# Brightside_Telemetry_stm_rev2.net
KiCad netlist of a schematic drawn in Altium Designer
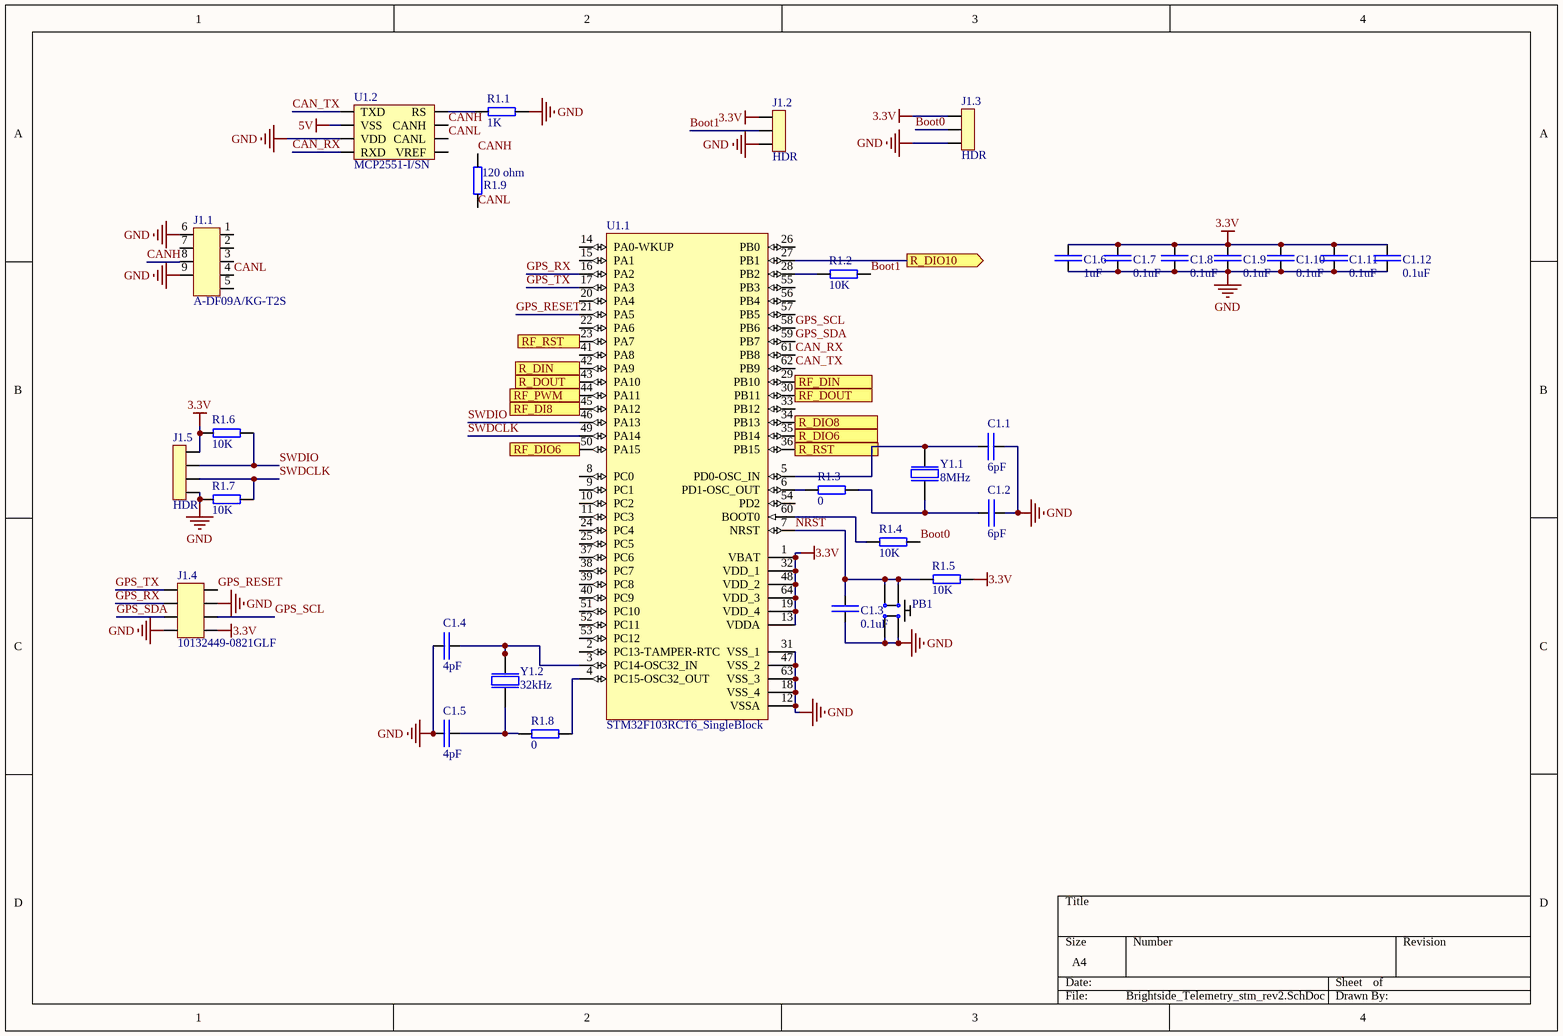
[diagram p0: Brightside_Telemetry_stm_rev2.SchDoc]

(export (version "E")
  (design (tool "Eeschema 10.0.6"))
  (components
    (comp (ref "C1.1")
      (value "6pF")
      (footprint "0603")
      (description "CAP CER 6PF 50V C0G/NPO 0603")
      (fields
        (field (name "MANUFACTURER") "Yageo")
        (field (name "MANUFACTURER PART NUMBER") "CC0603DRNPO9BN6R0")
      )
      (libsource (lib "Capacitors") (part "CC0603DRNPO9BN6R0"))
    )
    (comp (ref "C1.2")
      (value "6pF")
      (footprint "0603")
      (description "CAP CER 6PF 50V C0G/NPO 0603")
      (fields
        (field (name "MANUFACTURER") "Yageo")
        (field (name "MANUFACTURER PART NUMBER") "CC0603DRNPO9BN6R0")
      )
      (libsource (lib "Capacitors") (part "CC0603DRNPO9BN6R0"))
    )
    (comp (ref "C1.3")
      (value "0.1uF")
      (footprint "C0805")
      (description "CAP CER 0.1UF 50V X7R 0805")
      (fields
        (field (name "MANUFACTURER") "Samsung")
        (field (name "MANUFACTURER PART NUMBER") "CL21B104KBCWPNC")
      )
      (libsource (lib "Capacitors") (part "CL21B104KBCWPNC"))
    )
    (comp (ref "C1.4")
      (value "4pF")
      (footprint "0603")
      (description "CAP CER 4PF 50V C0G/NPO 0603")
      (fields
        (field (name "MANUFACTURER") "Yageo")
        (field (name "MANUFACTURER PART NUMBER") "CC0603CRNPO9BN4R0")
      )
      (libsource (lib "Capacitors") (part "CC0603CRNPO9BN4R0"))
    )
    (comp (ref "C1.5")
      (value "4pF")
      (footprint "0603")
      (description "CAP CER 4PF 50V C0G/NPO 0603")
      (fields
        (field (name "MANUFACTURER") "Yageo")
        (field (name "MANUFACTURER PART NUMBER") "CC0603CRNPO9BN4R0")
      )
      (libsource (lib "Capacitors") (part "CC0603CRNPO9BN4R0"))
    )
    (comp (ref "C1.6")
      (value "1uF")
      (footprint "1206")
      (description "CAP CER 1UF 16V X7R 1206")
      (fields
        (field (name "MANUFACTURER") "Wurth Electronics")
        (field (name "MANUFACTURER PART NUMBER") "885012208036")
      )
      (libsource (lib "Capacitors") (part "885012208036"))
    )
    (comp (ref "C1.7")
      (value "0.1uF")
      (footprint "C0805")
      (description "CAP CER 0.1UF 50V X7R 0805")
      (fields
        (field (name "MANUFACTURER") "Samsung")
        (field (name "MANUFACTURER PART NUMBER") "CL21B104KBCWPNC")
      )
      (libsource (lib "Capacitors") (part "CL21B104KBCWPNC"))
    )
    (comp (ref "C1.8")
      (value "0.1uF")
      (footprint "C0805")
      (description "CAP CER 0.1UF 50V X7R 0805")
      (fields
        (field (name "MANUFACTURER") "Samsung")
        (field (name "MANUFACTURER PART NUMBER") "CL21B104KBCWPNC")
      )
      (libsource (lib "Capacitors") (part "CL21B104KBCWPNC"))
    )
    (comp (ref "C1.9")
      (value "0.1uF")
      (footprint "C0805")
      (description "CAP CER 0.1UF 50V X7R 0805")
      (fields
        (field (name "MANUFACTURER") "Samsung")
        (field (name "MANUFACTURER PART NUMBER") "CL21B104KBCWPNC")
      )
      (libsource (lib "Capacitors") (part "CL21B104KBCWPNC"))
    )
    (comp (ref "C1.10")
      (value "0.1uF")
      (footprint "C0805")
      (description "CAP CER 0.1UF 50V X7R 0805")
      (fields
        (field (name "MANUFACTURER") "Samsung")
        (field (name "MANUFACTURER PART NUMBER") "CL21B104KBCWPNC")
      )
      (libsource (lib "Capacitors") (part "CL21B104KBCWPNC"))
    )
    (comp (ref "C1.11")
      (value "0.1uF")
      (footprint "C0805")
      (description "CAP CER 0.1UF 50V X7R 0805")
      (fields
        (field (name "MANUFACTURER") "Samsung")
        (field (name "MANUFACTURER PART NUMBER") "CL21B104KBCWPNC")
      )
      (libsource (lib "Capacitors") (part "CL21B104KBCWPNC"))
    )
    (comp (ref "C1.12")
      (value "0.1uF")
      (footprint "C0805")
      (description "CAP CER 0.1UF 50V X7R 0805")
      (fields
        (field (name "MANUFACTURER") "Samsung")
        (field (name "MANUFACTURER PART NUMBER") "CL21B104KBCWPNC")
      )
      (libsource (lib "Capacitors") (part "CL21B104KBCWPNC"))
    )
    (comp (ref "J1.1")
      (value "A-DF09A/KG-T2S")
      (footprint "DB9 (Female)")
      (description "FEMALE DB9 D-SUBMINIATURE CONNECTOR, CURRENT RATING 3A, VOLTAGE RATING 250VAC")
      (fields (field (name "MANUFACTURER") "Assmann"))
      (libsource (lib "Connectors") (part "A-DF09A/KG-T2S"))
    )
    (comp (ref "J1.2")
      (value "HDR")
      (footprint "0.1\" Header 3pos")
      (libsource (lib "Connectors") (part "0.1{dblquote} Header 3pos"))
    )
    (comp (ref "J1.3")
      (value "HDR")
      (footprint "0.1\" Header 3pos")
      (libsource (lib "Connectors") (part "0.1{dblquote} Header 3pos"))
    )
    (comp (ref "J1.4")
      (value "10132449-0821GLF")
      (footprint "Micro-Fit 3.0 8pos")
      (description "Micro-fit 3.0 8pos right-angle")
      (fields (field (name "MANUFACTURER") "Molex") (field (name "MANUFACTURER PART NUMBER") "43045-0800"))
      (libsource (lib "Connectors") (part "10132449-0821GLF"))
    )
    (comp (ref "J1.5")
      (value "HDR")
      (footprint "0.1\" Header 4pos")
      (libsource (lib "Connectors") (part "0.1{dblquote} Header 4pos"))
    )
    (comp (ref "PB1")
      (value "P12961SCT-ND")
      (footprint "P12961SCT-ND")
      (description "SWITCH TACTILE SPST-NO 0.02A 15V")
      (libsource (lib "Indication & Control") (part "P12961SCT-ND"))
    )
    (comp (ref "R1.1")
      (value "1K")
      (footprint "R0805")
      (description "RES SMD 1K OHM 1% 1/8W 0805")
      (fields
        (field (name "MANUFACTURER") "Panasonic")
        (field (name "MANUFACTURER PART NUMBER") "ERJ6ENF1001V")
      )
      (libsource (lib "Resistors") (part "ERJ6ENF1001V"))
    )
    (comp (ref "R1.2")
      (value "10K")
      (footprint "R0805")
      (description "RES SMD 10K OHM 1% 1/8W 0805")
      (fields (field (name "MANUFACTURER") "Yageo") (field (name "MANUFACTURER PART NUMBER") "ERJ-6ENF1002V"))
      (libsource (lib "Resistors") (part "ERJ6ENF1002V"))
    )
    (comp (ref "R1.3")
      (value "0")
      (footprint "0805")
      (fields
        (field (name "MANUFACTURER") "Stackpole Electronics")
        (field (name "MANUFACTURER PART NUMBER") "RMCF0805ZT0R00")
      )
      (libsource (lib "Resistors") (part "RMCF0805ZT0R00"))
    )
    (comp (ref "R1.4")
      (value "10K")
      (footprint "R0805")
      (description "RES SMD 10K OHM 1% 1/8W 0805")
      (fields (field (name "MANUFACTURER") "Yageo") (field (name "MANUFACTURER PART NUMBER") "ERJ-6ENF1002V"))
      (libsource (lib "Resistors") (part "ERJ6ENF1002V"))
    )
    (comp (ref "R1.5")
      (value "10K")
      (footprint "R0805")
      (description "RES SMD 10K OHM 1% 1/8W 0805")
      (fields (field (name "MANUFACTURER") "Yageo") (field (name "MANUFACTURER PART NUMBER") "ERJ-6ENF1002V"))
      (libsource (lib "Resistors") (part "ERJ6ENF1002V"))
    )
    (comp (ref "R1.6")
      (value "10K")
      (footprint "R0805")
      (description "RES SMD 10K OHM 1% 1/8W 0805")
      (fields (field (name "MANUFACTURER") "Yageo") (field (name "MANUFACTURER PART NUMBER") "ERJ-6ENF1002V"))
      (libsource (lib "Resistors") (part "ERJ6ENF1002V"))
    )
    (comp (ref "R1.7")
      (value "10K")
      (footprint "R0805")
      (description "RES SMD 10K OHM 1% 1/8W 0805")
      (fields (field (name "MANUFACTURER") "Yageo") (field (name "MANUFACTURER PART NUMBER") "ERJ-6ENF1002V"))
      (libsource (lib "Resistors") (part "ERJ6ENF1002V"))
    )
    (comp (ref "R1.8")
      (value "0")
      (footprint "0805")
      (fields
        (field (name "MANUFACTURER") "Stackpole Electronics")
        (field (name "MANUFACTURER PART NUMBER") "RMCF0805ZT0R00")
      )
      (libsource (lib "Resistors") (part "RMCF0805ZT0R00"))
    )
    (comp (ref "R1.9")
      (value "120 ohm")
      (footprint "R0805")
      (description "RES SMD 120 OHM 1% 1/8W 0805")
      (libsource (lib "Resistors") (part "ERJ6ENV1200V"))
    )
    (comp (ref "U1.1")
      (value "STM32F103RCT6_SingleBlock")
      (footprint "64-LQFP")
      (description "ARM® Cortex®-M3 STM32F1 Microcontroller IC 32-Bit 72MHz 256KB (256K x 8) FLASH")
      (libsource (lib "ICs") (part "STM32F103RCT6_SingleBlock"))
    )
    (comp (ref "U1.2")
      (value "MCP2551-I/SN")
      (footprint "8-SOIC")
      (description "CAN TRANSCEIVER")
      (fields (field (name "MANUFACTURER") "Microchip") (field (name "TOLERANCE") "20ppm"))
      (libsource (lib "ICs") (part "MCP2551-I/SN"))
    )
    (comp (ref "Y1.1")
      (value "8MHz")
      (footprint "NX8045GB-8.000000MHZ")
      (description "CRYSTAL 8.0000MHZ 8PF SMD")
      (fields
        (field (name "MANUFACTURER") "NDK")
        (field (name "MANUFACTURER PART NUMBER") "NX8045GB-8.000000MHZ")
      )
      (libsource (lib "Crystals") (part "NX8045GB-8.000000MHZ"))
    )
    (comp (ref "Y1.2")
      (value "32kHz")
      (footprint "FC-135 32.7680KA-AG")
      (description "Crystals 32.768KHz 20ppm 7.0pF -40C +85C")
      (fields
        (field (name "MANUFACTURER") "Epson")
        (field (name "MANUFACTURER PART NUMBER") "FC-13532.7680KA-AG0")
      )
      (libsource (lib "Crystals") (part "FC-13532.7680KA-AG0"))
    )
  )
  (nets
    (net (code "1") (name "/Boot0") (class "Default")
      (node (ref "J1.3") (pin "2") (pinfunction "2_2") (pintype "passive"))
      (node (ref "R1.4") (pin "2") (pinfunction "2_2") (pintype "passive"))
    )
    (net (code "2") (name "/Boot1") (class "Default")
      (node (ref "J1.2") (pin "2") (pinfunction "2_2") (pintype "passive"))
      (node (ref "R1.2") (pin "2") (pinfunction "2_2") (pintype "passive"))
    )
    (net (code "3") (name "/CANH") (class "Default")
      (node (ref "J1.1") (pin "8") (pinfunction "8_8") (pintype "passive"))
      (node (ref "R1.9") (pin "2") (pinfunction "2_2") (pintype "passive"))
      (node (ref "U1.2") (pin "7") (pinfunction "CANH_7") (pintype "passive"))
    )
    (net (code "4") (name "/CANL") (class "Default")
      (node (ref "J1.1") (pin "4") (pinfunction "4_4") (pintype "passive"))
      (node (ref "R1.9") (pin "1") (pinfunction "1_1") (pintype "passive"))
      (node (ref "U1.2") (pin "6") (pinfunction "CANL_6") (pintype "passive"))
    )
    (net (code "5") (name "/CAN_RX") (class "Default")
      (node (ref "U1.1") (pin "61") (pinfunction "PB8_61") (pintype "bidirectional"))
      (node (ref "U1.2") (pin "4") (pinfunction "RXD_4") (pintype "passive"))
    )
    (net (code "6") (name "/CAN_TX") (class "Default")
      (node (ref "U1.1") (pin "62") (pinfunction "PB9_62") (pintype "bidirectional"))
      (node (ref "U1.2") (pin "1") (pinfunction "TXD_1") (pintype "passive"))
    )
    (net (code "7") (name "/GPS_RESET") (class "Default")
      (node (ref "J1.4") (pin "1") (pinfunction "1_1") (pintype "passive"))
      (node (ref "U1.1") (pin "21") (pinfunction "PA5_21") (pintype "bidirectional"))
    )
    (net (code "8") (name "/GPS_RX") (class "Default")
      (node (ref "J1.4") (pin "6") (pinfunction "6_6") (pintype "passive"))
      (node (ref "U1.1") (pin "16") (pinfunction "PA2_16") (pintype "bidirectional"))
    )
    (net (code "9") (name "/GPS_SCL") (class "Default")
      (node (ref "J1.4") (pin "3") (pinfunction "3_3") (pintype "passive"))
      (node (ref "U1.1") (pin "58") (pinfunction "PB6_58") (pintype "bidirectional"))
    )
    (net (code "10") (name "/GPS_SDA") (class "Default")
      (node (ref "J1.4") (pin "7") (pinfunction "7_7") (pintype "passive"))
      (node (ref "U1.1") (pin "59") (pinfunction "PB7_59") (pintype "bidirectional"))
    )
    (net (code "11") (name "/GPS_TX") (class "Default")
      (node (ref "J1.4") (pin "5") (pinfunction "5_5") (pintype "passive"))
      (node (ref "U1.1") (pin "17") (pinfunction "PA3_17") (pintype "bidirectional"))
    )
    (net (code "12") (name "/NRST") (class "Default")
      (node (ref "C1.3") (pin "2") (pinfunction "2_2") (pintype "passive"))
      (node (ref "PB1") (pin "1") (pinfunction "A_1") (pintype "passive"))
      (node (ref "PB1") (pin "3") (pinfunction "B_3") (pintype "passive"))
      (node (ref "R1.5") (pin "1") (pinfunction "1_1") (pintype "passive"))
      (node (ref "U1.1") (pin "7") (pinfunction "NRST_7") (pintype "bidirectional"))
    )
    (net (code "13") (name "/RF_DI8") (class "Default")
      (node (ref "U1.1") (pin "45") (pinfunction "PA12_45") (pintype "bidirectional"))
    )
    (net (code "15") (name "/RF_DIN") (class "Default")
      (node (ref "U1.1") (pin "29") (pinfunction "PB10_29") (pintype "bidirectional"))
    )
    (net (code "17") (name "/RF_DIO6") (class "Default")
      (node (ref "U1.1") (pin "50") (pinfunction "PA15_50") (pintype "bidirectional"))
    )
    (net (code "18") (name "/RF_DOUT") (class "Default")
      (node (ref "U1.1") (pin "30") (pinfunction "PB11_30") (pintype "bidirectional"))
    )
    (net (code "19") (name "/RF_PWM") (class "Default")
      (node (ref "U1.1") (pin "44") (pinfunction "PA11_44") (pintype "bidirectional"))
    )
    (net (code "22") (name "/RF_RST") (class "Default")
      (node (ref "U1.1") (pin "23") (pinfunction "PA7_23") (pintype "bidirectional"))
    )
    (net (code "23") (name "/R_DIN") (class "Default")
      (node (ref "U1.1") (pin "42") (pinfunction "PA9_42") (pintype "bidirectional"))
    )
    (net (code "25") (name "/R_DIO6") (class "Default")
      (node (ref "U1.1") (pin "35") (pinfunction "PB14_35") (pintype "bidirectional"))
    )
    (net (code "26") (name "/R_DIO8") (class "Default")
      (node (ref "U1.1") (pin "34") (pinfunction "PB13_34") (pintype "bidirectional"))
    )
    (net (code "27") (name "/R_DIO10") (class "Default")
      (node (ref "U1.1") (pin "27") (pinfunction "PB1_27") (pintype "bidirectional"))
    )
    (net (code "28") (name "/R_DOUT") (class "Default")
      (node (ref "U1.1") (pin "43") (pinfunction "PA10_43") (pintype "bidirectional"))
    )
    (net (code "29") (name "/R_RST") (class "Default")
      (node (ref "U1.1") (pin "36") (pinfunction "PB15_36") (pintype "bidirectional"))
    )
    (net (code "30") (name "/SWDCLK") (class "Default")
      (node (ref "J1.5") (pin "2") (pinfunction "2_2") (pintype "passive"))
      (node (ref "R1.7") (pin "2") (pinfunction "2_2") (pintype "passive"))
      (node (ref "U1.1") (pin "49") (pinfunction "PA14_49") (pintype "bidirectional"))
    )
    (net (code "31") (name "/SWDIO") (class "Default")
      (node (ref "J1.5") (pin "3") (pinfunction "3_3") (pintype "passive"))
      (node (ref "R1.6") (pin "2") (pinfunction "2_2") (pintype "passive"))
      (node (ref "U1.1") (pin "46") (pinfunction "PA13_46") (pintype "bidirectional"))
    )
    (net (code "32") (name "3.3V") (class "Default")
      (node (ref "C1.10") (pin "2") (pinfunction "2_2") (pintype "passive"))
      (node (ref "C1.11") (pin "2") (pinfunction "2_2") (pintype "passive"))
      (node (ref "C1.12") (pin "2") (pinfunction "2_2") (pintype "passive"))
      (node (ref "C1.6") (pin "1") (pinfunction "1_1") (pintype "passive"))
      (node (ref "C1.7") (pin "2") (pinfunction "2_2") (pintype "passive"))
      (node (ref "C1.8") (pin "2") (pinfunction "2_2") (pintype "passive"))
      (node (ref "C1.9") (pin "2") (pinfunction "2_2") (pintype "passive"))
      (node (ref "J1.2") (pin "1") (pinfunction "1_1") (pintype "passive"))
      (node (ref "J1.3") (pin "1") (pinfunction "1_1") (pintype "passive"))
      (node (ref "J1.4") (pin "4") (pinfunction "4_4") (pintype "passive"))
      (node (ref "J1.5") (pin "4") (pinfunction "4_4") (pintype "passive"))
      (node (ref "R1.5") (pin "2") (pinfunction "2_2") (pintype "passive"))
      (node (ref "R1.6") (pin "1") (pinfunction "1_1") (pintype "passive"))
      (node (ref "U1.1") (pin "1") (pinfunction "VBAT_1") (pintype "power_in"))
      (node (ref "U1.1") (pin "13") (pinfunction "VDDA_13") (pintype "power_in"))
      (node (ref "U1.1") (pin "19") (pinfunction "VDD_4_19") (pintype "power_in"))
      (node (ref "U1.1") (pin "32") (pinfunction "VDD_1_32") (pintype "power_in"))
      (node (ref "U1.1") (pin "48") (pinfunction "VDD_2_48") (pintype "power_in"))
      (node (ref "U1.1") (pin "64") (pinfunction "VDD_3_64") (pintype "power_in"))
    )
    (net (code "33") (name "5V") (class "Default")
      (node (ref "U1.2") (pin "2") (pinfunction "VSS_2") (pintype "passive"))
    )
    (net (code "34") (name "GND") (class "Default")
      (node (ref "C1.1") (pin "2") (pinfunction "2_2") (pintype "passive"))
      (node (ref "C1.10") (pin "1") (pinfunction "1_1") (pintype "passive"))
      (node (ref "C1.11") (pin "1") (pinfunction "1_1") (pintype "passive"))
      (node (ref "C1.12") (pin "1") (pinfunction "1_1") (pintype "passive"))
      (node (ref "C1.2") (pin "2") (pinfunction "2_2") (pintype "passive"))
      (node (ref "C1.3") (pin "1") (pinfunction "1_1") (pintype "passive"))
      (node (ref "C1.4") (pin "1") (pinfunction "1_1") (pintype "passive"))
      (node (ref "C1.5") (pin "1") (pinfunction "1_1") (pintype "passive"))
      (node (ref "C1.6") (pin "2") (pinfunction "2_2") (pintype "passive"))
      (node (ref "C1.7") (pin "1") (pinfunction "1_1") (pintype "passive"))
      (node (ref "C1.8") (pin "1") (pinfunction "1_1") (pintype "passive"))
      (node (ref "C1.9") (pin "1") (pinfunction "1_1") (pintype "passive"))
      (node (ref "J1.1") (pin "6") (pinfunction "6_6") (pintype "passive"))
      (node (ref "J1.1") (pin "9") (pinfunction "9_9") (pintype "passive"))
      (node (ref "J1.2") (pin "3") (pinfunction "3_3") (pintype "passive"))
      (node (ref "J1.3") (pin "3") (pinfunction "3_3") (pintype "passive"))
      (node (ref "J1.4") (pin "2") (pinfunction "2_2") (pintype "passive"))
      (node (ref "J1.4") (pin "8") (pinfunction "8_8") (pintype "passive"))
      (node (ref "J1.5") (pin "1") (pinfunction "1_1") (pintype "passive"))
      (node (ref "PB1") (pin "2") (pinfunction "A'_2") (pintype "passive"))
      (node (ref "PB1") (pin "4") (pinfunction "B'_4") (pintype "passive"))
      (node (ref "R1.1") (pin "2") (pinfunction "2_2") (pintype "passive"))
      (node (ref "R1.7") (pin "1") (pinfunction "1_1") (pintype "passive"))
      (node (ref "U1.1") (pin "12") (pinfunction "VSSA_12") (pintype "power_in"))
      (node (ref "U1.1") (pin "18") (pinfunction "VSS_4_18") (pintype "power_in"))
      (node (ref "U1.1") (pin "31") (pinfunction "VSS_1_31") (pintype "power_in"))
      (node (ref "U1.1") (pin "47") (pinfunction "VSS_2_47") (pintype "power_in"))
      (node (ref "U1.1") (pin "63") (pinfunction "VSS_3_63") (pintype "power_in"))
      (node (ref "U1.2") (pin "3") (pinfunction "VDD_3") (pintype "passive"))
    )
    (net (code "35") (name "Net-(C1.2-Pad1)") (class "Default")
      (node (ref "C1.2") (pin "1") (pinfunction "1_1") (pintype "passive"))
      (node (ref "R1.3") (pin "2") (pinfunction "2_2") (pintype "passive"))
      (node (ref "Y1.1") (pin "1") (pinfunction "1_1") (pintype "passive"))
    )
    (net (code "36") (name "Net-(C1.5-Pad2)") (class "Default")
      (node (ref "C1.5") (pin "2") (pinfunction "2_2") (pintype "passive"))
      (node (ref "R1.8") (pin "1") (pinfunction "1_1") (pintype "passive"))
      (node (ref "Y1.2") (pin "2") (pinfunction "2_2") (pintype "passive"))
    )
    (net (code "37") (name "Net-(U1.1-BOOT0)") (class "Default")
      (node (ref "R1.4") (pin "1") (pinfunction "1_1") (pintype "passive"))
      (node (ref "U1.1") (pin "60") (pinfunction "BOOT0_60") (pintype "input"))
    )
    (net (code "38") (name "Net-(U1.1-PB2)") (class "Default")
      (node (ref "R1.2") (pin "1") (pinfunction "1_1") (pintype "passive"))
      (node (ref "U1.1") (pin "28") (pinfunction "PB2_28") (pintype "bidirectional"))
    )
    (net (code "39") (name "Net-(U1.1-PC14-OSC32_IN)") (class "Default")
      (node (ref "C1.4") (pin "2") (pinfunction "2_2") (pintype "passive"))
      (node (ref "U1.1") (pin "3") (pinfunction "PC14-OSC32_IN_3") (pintype "bidirectional"))
      (node (ref "Y1.2") (pin "1") (pinfunction "1_1") (pintype "passive"))
    )
    (net (code "40") (name "Net-(U1.1-PC15-OSC32_OUT)") (class "Default")
      (node (ref "R1.8") (pin "2") (pinfunction "2_2") (pintype "passive"))
      (node (ref "U1.1") (pin "4") (pinfunction "PC15-OSC32_OUT_4") (pintype "bidirectional"))
    )
    (net (code "41") (name "Net-(U1.1-PD0-OSC_IN)") (class "Default")
      (node (ref "C1.1") (pin "1") (pinfunction "1_1") (pintype "passive"))
      (node (ref "U1.1") (pin "5") (pinfunction "PD0-OSC_IN_5") (pintype "bidirectional"))
      (node (ref "Y1.1") (pin "2") (pinfunction "2_2") (pintype "passive"))
    )
    (net (code "42") (name "Net-(U1.1-PD1-OSC_OUT)") (class "Default")
      (node (ref "R1.3") (pin "1") (pinfunction "1_1") (pintype "passive"))
      (node (ref "U1.1") (pin "6") (pinfunction "PD1-OSC_OUT_6") (pintype "bidirectional"))
    )
    (net (code "43") (name "Net-(U1.2-RS)") (class "Default")
      (node (ref "R1.1") (pin "1") (pinfunction "1_1") (pintype "passive"))
      (node (ref "U1.2") (pin "8") (pinfunction "RS_8") (pintype "passive"))
    )
    (net (code "44") (name "unconnected-(J1.1-Pad1)") (class "Default")
      (node (ref "J1.1") (pin "1") (pinfunction "1_1") (pintype "passive"))
    )
    (net (code "45") (name "unconnected-(J1.1-Pad2)") (class "Default")
      (node (ref "J1.1") (pin "2") (pinfunction "2_2") (pintype "passive"))
    )
    (net (code "46") (name "unconnected-(J1.1-Pad3)") (class "Default")
      (node (ref "J1.1") (pin "3") (pinfunction "3_3") (pintype "passive"))
    )
    (net (code "47") (name "unconnected-(J1.1-Pad5)") (class "Default")
      (node (ref "J1.1") (pin "5") (pinfunction "5_5") (pintype "passive"))
    )
    (net (code "48") (name "unconnected-(J1.1-Pad7)") (class "Default")
      (node (ref "J1.1") (pin "7") (pinfunction "7_7") (pintype "passive"))
    )
    (net (code "49") (name "unconnected-(U1.1-PA0-WKUP-Pad14)") (class "Default")
      (node (ref "U1.1") (pin "14") (pinfunction "PA0-WKUP_14") (pintype "bidirectional"))
    )
    (net (code "50") (name "unconnected-(U1.1-PA1-Pad15)") (class "Default")
      (node (ref "U1.1") (pin "15") (pinfunction "PA1_15") (pintype "bidirectional"))
    )
    (net (code "51") (name "unconnected-(U1.1-PA4-Pad20)") (class "Default")
      (node (ref "U1.1") (pin "20") (pinfunction "PA4_20") (pintype "bidirectional"))
    )
    (net (code "52") (name "unconnected-(U1.1-PA6-Pad22)") (class "Default")
      (node (ref "U1.1") (pin "22") (pinfunction "PA6_22") (pintype "bidirectional"))
    )
    (net (code "53") (name "unconnected-(U1.1-PA8-Pad41)") (class "Default")
      (node (ref "U1.1") (pin "41") (pinfunction "PA8_41") (pintype "bidirectional"))
    )
    (net (code "54") (name "unconnected-(U1.1-PB0-Pad26)") (class "Default")
      (node (ref "U1.1") (pin "26") (pinfunction "PB0_26") (pintype "bidirectional"))
    )
    (net (code "55") (name "unconnected-(U1.1-PB3-Pad55)") (class "Default")
      (node (ref "U1.1") (pin "55") (pinfunction "PB3_55") (pintype "bidirectional"))
    )
    (net (code "56") (name "unconnected-(U1.1-PB4-Pad56)") (class "Default")
      (node (ref "U1.1") (pin "56") (pinfunction "PB4_56") (pintype "bidirectional"))
    )
    (net (code "57") (name "unconnected-(U1.1-PB5-Pad57)") (class "Default")
      (node (ref "U1.1") (pin "57") (pinfunction "PB5_57") (pintype "bidirectional"))
    )
    (net (code "58") (name "unconnected-(U1.1-PB12-Pad33)") (class "Default")
      (node (ref "U1.1") (pin "33") (pinfunction "PB12_33") (pintype "bidirectional"))
    )
    (net (code "59") (name "unconnected-(U1.1-PC0-Pad8)") (class "Default")
      (node (ref "U1.1") (pin "8") (pinfunction "PC0_8") (pintype "bidirectional"))
    )
    (net (code "60") (name "unconnected-(U1.1-PC1-Pad9)") (class "Default")
      (node (ref "U1.1") (pin "9") (pinfunction "PC1_9") (pintype "bidirectional"))
    )
    (net (code "61") (name "unconnected-(U1.1-PC2-Pad10)") (class "Default")
      (node (ref "U1.1") (pin "10") (pinfunction "PC2_10") (pintype "bidirectional"))
    )
    (net (code "62") (name "unconnected-(U1.1-PC3-Pad11)") (class "Default")
      (node (ref "U1.1") (pin "11") (pinfunction "PC3_11") (pintype "bidirectional"))
    )
    (net (code "63") (name "unconnected-(U1.1-PC4-Pad24)") (class "Default")
      (node (ref "U1.1") (pin "24") (pinfunction "PC4_24") (pintype "bidirectional"))
    )
    (net (code "64") (name "unconnected-(U1.1-PC5-Pad25)") (class "Default")
      (node (ref "U1.1") (pin "25") (pinfunction "PC5_25") (pintype "bidirectional"))
    )
    (net (code "65") (name "unconnected-(U1.1-PC6-Pad37)") (class "Default")
      (node (ref "U1.1") (pin "37") (pinfunction "PC6_37") (pintype "bidirectional"))
    )
    (net (code "66") (name "unconnected-(U1.1-PC7-Pad38)") (class "Default")
      (node (ref "U1.1") (pin "38") (pinfunction "PC7_38") (pintype "bidirectional"))
    )
    (net (code "67") (name "unconnected-(U1.1-PC8-Pad39)") (class "Default")
      (node (ref "U1.1") (pin "39") (pinfunction "PC8_39") (pintype "bidirectional"))
    )
    (net (code "68") (name "unconnected-(U1.1-PC9-Pad40)") (class "Default")
      (node (ref "U1.1") (pin "40") (pinfunction "PC9_40") (pintype "bidirectional"))
    )
    (net (code "69") (name "unconnected-(U1.1-PC10-Pad51)") (class "Default")
      (node (ref "U1.1") (pin "51") (pinfunction "PC10_51") (pintype "bidirectional"))
    )
    (net (code "70") (name "unconnected-(U1.1-PC11-Pad52)") (class "Default")
      (node (ref "U1.1") (pin "52") (pinfunction "PC11_52") (pintype "bidirectional"))
    )
    (net (code "71") (name "unconnected-(U1.1-PC12-Pad53)") (class "Default")
      (node (ref "U1.1") (pin "53") (pinfunction "PC12_53") (pintype "bidirectional"))
    )
    (net (code "72") (name "unconnected-(U1.1-PC13-TAMPER-RTC-Pad2)") (class "Default")
      (node (ref "U1.1") (pin "2") (pinfunction "PC13-TAMPER-RTC_2") (pintype "bidirectional"))
    )
    (net (code "73") (name "unconnected-(U1.1-PD2-Pad54)") (class "Default")
      (node (ref "U1.1") (pin "54") (pinfunction "PD2_54") (pintype "bidirectional"))
    )
    (net (code "74") (name "unconnected-(U1.2-VREF-Pad5)") (class "Default")
      (node (ref "U1.2") (pin "5") (pinfunction "VREF_5") (pintype "passive"))
    )
  )
)
